# Sheet1.net
KiCad netlist of a schematic drawn in Altium Designer
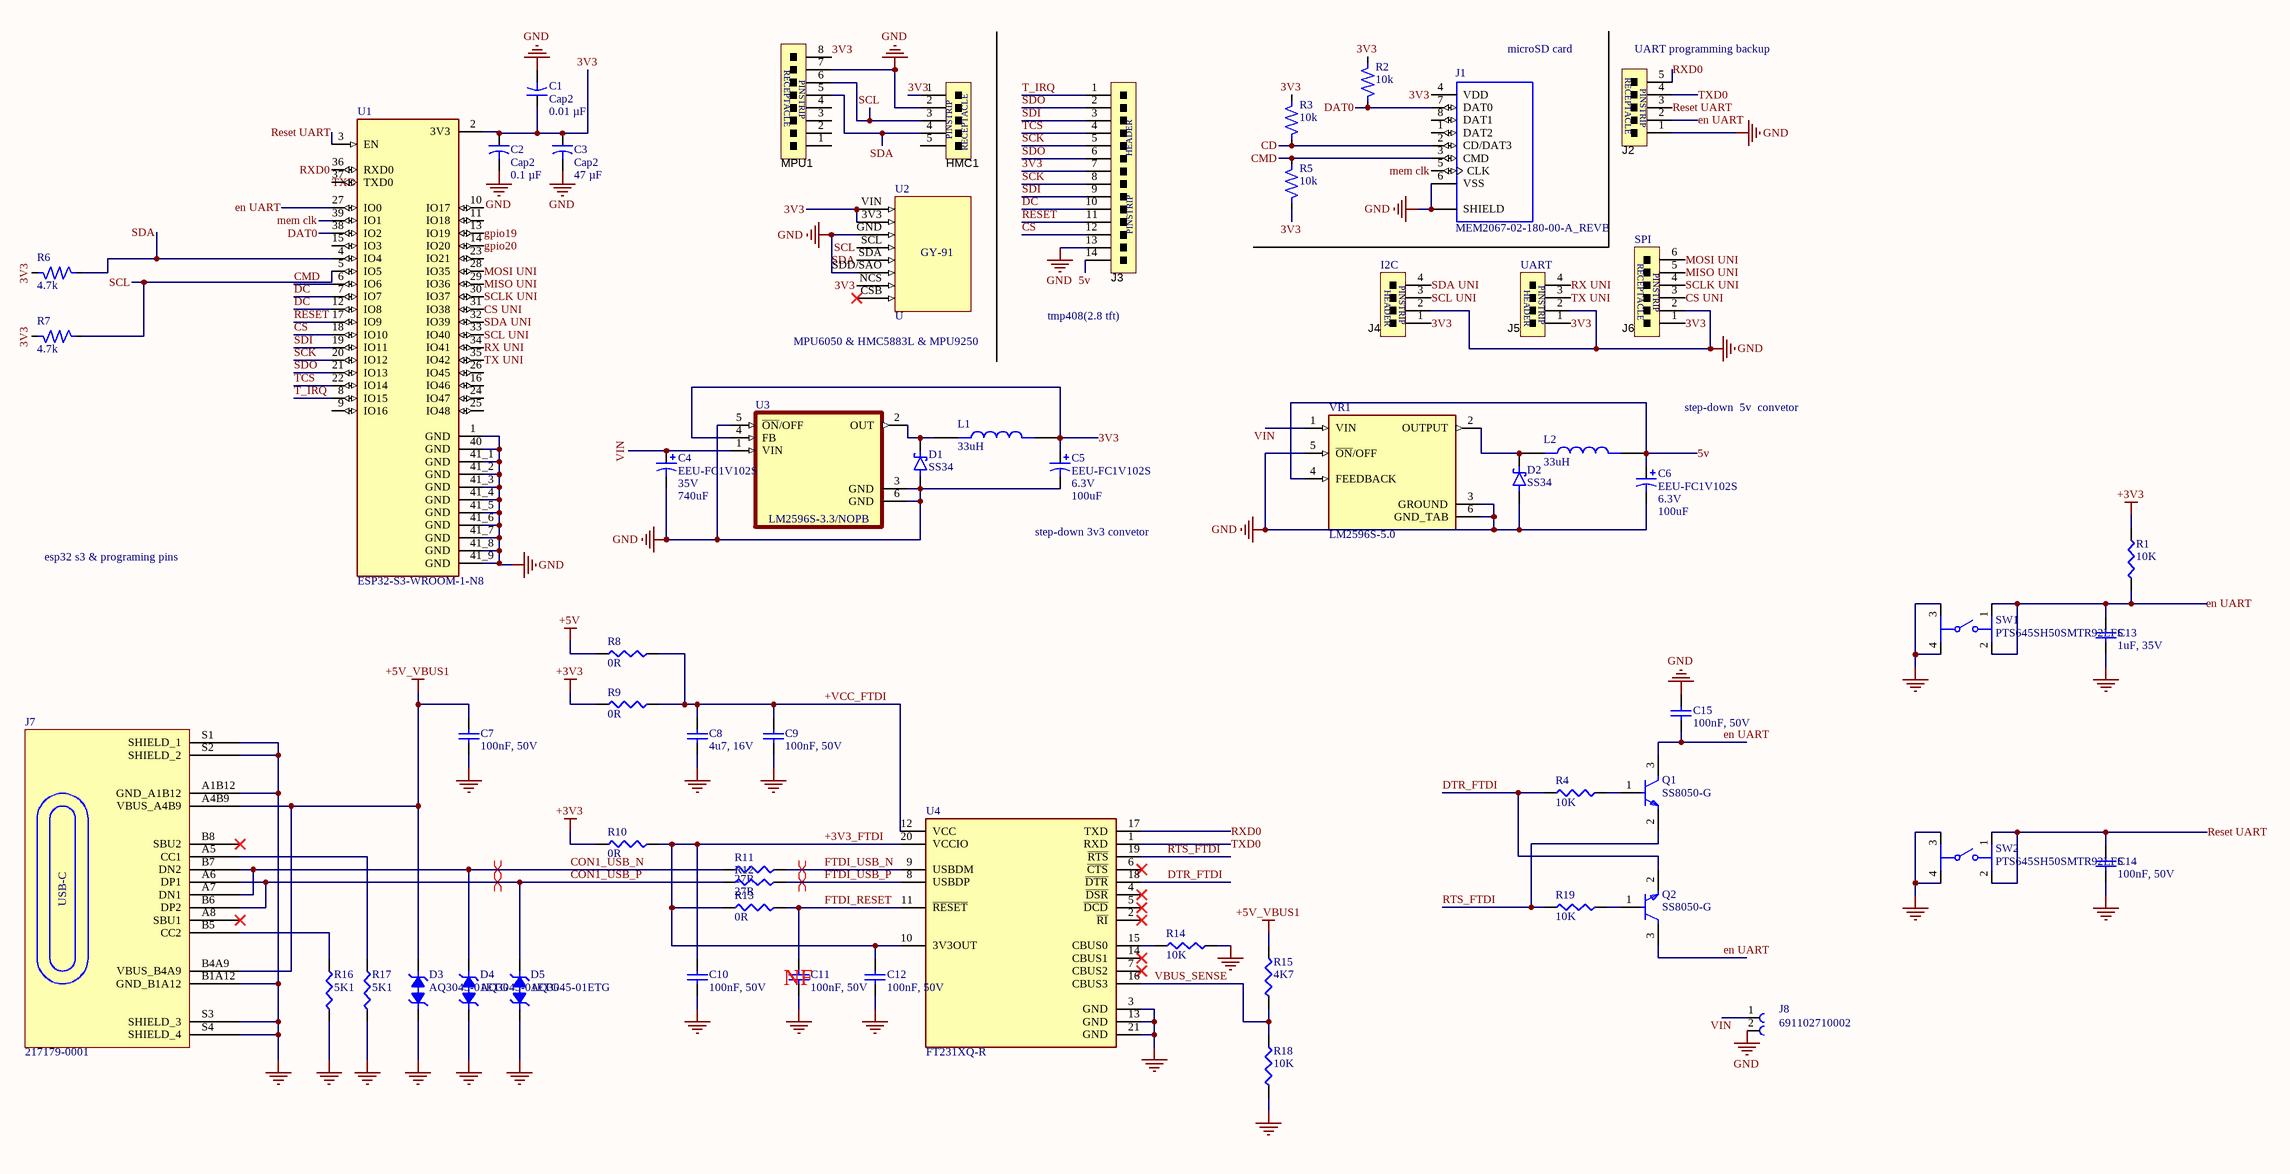
[diagram p0: Sheet1.SchDoc]

(export (version "E")
  (design (tool "Eeschema 10.0.6"))
  (components
    (comp (ref "C1")
      (value "Cap2")
      (footprint "CAPR5-4X5")
      (description "Capacitor")
      (fields (field (name "ALTIUM_VALUE") "0.01 µF") (field (name "PUBLISHER") "Altium Limited"))
      (libsource (lib "Miscellaneous Devices") (part "Cap2"))
    )
    (comp (ref "C2")
      (value "Cap2")
      (footprint "CAPR5-4X5")
      (description "Capacitor")
      (fields (field (name "ALTIUM_VALUE") "0.1 µF") (field (name "PUBLISHER") "Altium Limited"))
      (libsource (lib "Miscellaneous Devices") (part "Cap2"))
    )
    (comp (ref "C3")
      (value "Cap2")
      (footprint "CAPR5-4X5")
      (description "Capacitor")
      (fields (field (name "ALTIUM_VALUE") "47 µF") (field (name "PUBLISHER") "Altium Limited"))
      (libsource (lib "Miscellaneous Devices") (part "Cap2"))
    )
    (comp (ref "C4")
      (value "EEU-FC1V102S")
      (footprint "THRU-KMG-L25")
      (description "1000uF, Alum Electrolytic Capacitor, 35V, 16mm x 20mm, lead spacing 7.5mm")
      (fields
        (field (name "MANUFACTURER") "Panasonic")
        (field (name "VOLTAGEDC") "35V")
        (field (name "ALTIUM_VALUE") "740uF")
      )
      (libsource (lib "Caps") (part "1000uF"))
    )
    (comp (ref "C5")
      (value "EEU-FC1V102S")
      (footprint "THRU-KMG-L25")
      (description "1000uF, Alum Electrolytic Capacitor, 35V, 16mm x 20mm, lead spacing 7.5mm")
      (fields
        (field (name "MANUFACTURER") "Panasonic")
        (field (name "VOLTAGEDC") "6.3V")
        (field (name "ALTIUM_VALUE") "100uF")
      )
      (libsource (lib "Caps") (part "1000uF"))
    )
    (comp (ref "C6")
      (value "EEU-FC1V102S")
      (footprint "THRU-KMG-L25")
      (description "1000uF, Alum Electrolytic Capacitor, 35V, 16mm x 20mm, lead spacing 7.5mm")
      (fields
        (field (name "MANUFACTURER") "Panasonic")
        (field (name "VOLTAGEDC") "6.3V")
        (field (name "ALTIUM_VALUE") "100uF")
      )
      (libsource (lib "Caps") (part "1000uF"))
    )
    (comp (ref "C7")
      (value "100nF, 50V")
      (footprint "CAPC1005X55N")
      (description "CAP CER 0.1UF 50V X7R 0402")
      (fields
        (field (name "MANUFACTURER") "Samsung")
        (field (name "MANUFACTURER PART NUMBER") "CL05B104KB54PNC")
      )
      (libsource (lib "Schlib") (part "CL05B104KB54PNC"))
    )
    (comp (ref "C8")
      (value "4u7, 16V")
      (footprint "CAPC1005X55N")
      (description "CAP CER 4.7UF 16V X5R 0402")
      (fields
        (field (name "MANUFACTURER") "Samsung")
        (field (name "MANUFACTURER PART NUMBER") "CL05A475MO5NUNC")
      )
      (libsource (lib "Schlib") (part "CL05A475MO5NUNC"))
    )
    (comp (ref "C9")
      (value "100nF, 50V")
      (footprint "CAPC1005X55N")
      (description "CAP CER 0.1UF 50V X7R 0402")
      (fields
        (field (name "MANUFACTURER") "Samsung")
        (field (name "MANUFACTURER PART NUMBER") "CL05B104KB54PNC")
      )
      (libsource (lib "Schlib") (part "CL05B104KB54PNC"))
    )
    (comp (ref "C10")
      (value "100nF, 50V")
      (footprint "CAPC1005X55N")
      (description "CAP CER 0.1UF 50V X7R 0402")
      (fields
        (field (name "MANUFACTURER") "Samsung")
        (field (name "MANUFACTURER PART NUMBER") "CL05B104KB54PNC")
      )
      (libsource (lib "Schlib") (part "CL05B104KB54PNC"))
    )
    (comp (ref "C11")
      (value "100nF, 50V")
      (footprint "CAPC1005X55N")
      (description "CAP CER 0.1UF 50V X7R 0402")
      (fields
        (field (name "MANUFACTURER") "Samsung")
        (field (name "MANUFACTURER PART NUMBER") "CL05B104KB54PNC")
      )
      (libsource (lib "Schlib") (part "CL05B104KB54PNC"))
    )
    (comp (ref "C12")
      (value "100nF, 50V")
      (footprint "CAPC1005X55N")
      (description "CAP CER 0.1UF 50V X7R 0402")
      (fields
        (field (name "MANUFACTURER") "Samsung")
        (field (name "MANUFACTURER PART NUMBER") "CL05B104KB54PNC")
      )
      (libsource (lib "Schlib") (part "CL05B104KB54PNC"))
    )
    (comp (ref "C13")
      (value "1uF, 35V")
      (footprint "CAPC1005X55N")
      (description "CAP CER 1UF 35V X5R 0402")
      (fields
        (field (name "MANUFACTURER") "Samsung")
        (field (name "MANUFACTURER PART NUMBER") "CL05A105KL5NRNC")
      )
      (libsource (lib "Schlib") (part "CL05A105KL5NRNC"))
    )
    (comp (ref "C14")
      (value "100nF, 50V")
      (footprint "CAPC1005X55N")
      (description "CAP CER 0.1UF 50V X7R 0402")
      (fields
        (field (name "MANUFACTURER") "Samsung")
        (field (name "MANUFACTURER PART NUMBER") "CL05B104KB54PNC")
      )
      (libsource (lib "Schlib") (part "CL05B104KB54PNC"))
    )
    (comp (ref "C15")
      (value "100nF, 50V")
      (footprint "CAPC1005X55N")
      (description "CAP CER 0.1UF 50V X7R 0402")
      (fields
        (field (name "MANUFACTURER") "Samsung")
        (field (name "MANUFACTURER PART NUMBER") "CL05B104KB54PNC")
      )
      (libsource (lib "Schlib") (part "CL05B104KB54PNC"))
    )
    (comp (ref "D1")
      (value "SS34")
      (footprint "DIO_SS34")
      (description "3A, 40V, Schottky Rectifier")
      (fields (field (name "MF") "Taiwan Semiconductor"))
      (libsource (lib "SS34") (part "SS34"))
    )
    (comp (ref "D2")
      (value "SS34")
      (footprint "DIO_SS34")
      (description "3A, 40V, Schottky Rectifier")
      (fields (field (name "MF") "Taiwan Semiconductor"))
      (libsource (lib "SS34") (part "SS34"))
    )
    (comp (ref "D3")
      (value "AQ3045-01ETG")
      (footprint "SOD882")
      (description "TVS DIODE 5.3VWM 12VC SOD882")
      (fields (field (name "MANUFACTURER") "Littelfuse") (field (name "LCSC PART NUMBER") "C3710326"))
      (libsource (lib "Schlib") (part "AQ3045-01ETG"))
    )
    (comp (ref "D4")
      (value "AQ3045-01ETG")
      (footprint "SOD882")
      (description "TVS DIODE 5.3VWM 12VC SOD882")
      (fields (field (name "MANUFACTURER") "Littelfuse") (field (name "LCSC PART NUMBER") "C3710326"))
      (libsource (lib "Schlib") (part "AQ3045-01ETG"))
    )
    (comp (ref "D5")
      (value "AQ3045-01ETG")
      (footprint "SOD882")
      (description "TVS DIODE 5.3VWM 12VC SOD882")
      (fields (field (name "MANUFACTURER") "Littelfuse") (field (name "LCSC PART NUMBER") "C3710326"))
      (libsource (lib "Schlib") (part "AQ3045-01ETG"))
    )
    (comp (ref "HMC1")
      (value "5-534237-3")
      (footprint "PINSTRIP-SINGLE-5PIN-.1")
      (description "5 Pin Receptacle, Single row, 2.54mm pitch, Vertical")
      (fields (field (name "MANUFACTURER") "TE Connectivity"))
      (libsource (lib "CONNECTORS - PIN HEADERS") (part "PINSTRIP-RCPT-SINGLE-5pin"))
    )
    (comp (ref "J1")
      (value "MEM2067-02-180-00-A_REVB")
      (footprint "GCT_MEM2067-02-180-00-A_REVB")
      (description "Micro SD Memory Card ConnectorSMT, Hinged, 1.80mm Profile")
      (libsource (lib "MEM2067-02-180-00-A_REVB") (part "MEM2067-02-180-00-A_REVB"))
    )
    (comp (ref "J2")
      (value "5-534237-3")
      (footprint "PINSTRIP-SINGLE-5PIN-.1")
      (description "5 Pin Receptacle, Single row, 2.54mm pitch, Vertical")
      (fields (field (name "MANUFACTURER") "TE Connectivity"))
      (libsource (lib "") (part "PINSTRIP-RCPT-SINGLE-5pin_1"))
    )
    (comp (ref "J3")
      (value "9-146285-0")
      (footprint "PINSTRIP-SINGLE-14PIN-.1")
      (description "14 Pin Header, Single row, 2.54mm pitch, Unshrouded Pin Strip, Vertical")
      (fields
        (field (name "MANUFACTURER") "TE Connectivity")
        (field (name "PART NUMBER") "14/40 of 9-146285-0")
      )
      (libsource (lib "CONNECTORS - PIN HEADERS") (part "PINSTRIP-HDR-SINGLE-14pin"))
    )
    (comp (ref "J4")
      (value "9-146285-0")
      (footprint "PINSTRIP-SINGLE-4PIN-.1")
      (description "4 Pin Header, Single row, 2.54mm pitch, Unshrouded Pin Strip, Vertical")
      (fields
        (field (name "MANUFACTURER") "TE Connectivity")
        (field (name "PART NUMBER") "04/40 of 9-146285-0")
      )
      (libsource (lib "CONNECTORS - PIN HEADERS") (part "PINSTRIP-HDR-SINGLE-4pin"))
    )
    (comp (ref "J5")
      (value "9-146285-0")
      (footprint "PINSTRIP-SINGLE-4PIN-.1")
      (description "4 Pin Header, Single row, 2.54mm pitch, Unshrouded Pin Strip, Vertical")
      (fields
        (field (name "MANUFACTURER") "TE Connectivity")
        (field (name "PART NUMBER") "04/40 of 9-146285-0")
      )
      (libsource (lib "CONNECTORS - PIN HEADERS") (part "PINSTRIP-HDR-SINGLE-4pin"))
    )
    (comp (ref "J6")
      (value "5-534237-4")
      (footprint "PINSTRIP-SINGLE-6PIN-.1")
      (description "6 Pin Receptacle, Single row, 2.54mm pitch, Vertical")
      (fields (field (name "MANUFACTURER") "TE Connectivity"))
      (libsource (lib "CONNECTORS - PIN HEADERS") (part "PINSTRIP-RCPT-SINGLE-6pin"))
    )
    (comp (ref "J7")
      (value "217179-0001")
      (footprint "FP-2171790001-MFG")
      (description "CONN RCP USB2.0 TYP C 24P SMD RA")
      (fields (field (name "MANUFACTURER") "Molex") (field (name "LCSC PART NUMBER") "C3197684"))
      (libsource (lib "Schlib") (part "217179-0001"))
    )
    (comp (ref "J8")
      (value "691102710002")
      (footprint "*691102710002")
      (description "102 Series 5mm Pitch Straight, PCB Terminal Block, Through Hole, 2 Way")
      (fields (field (name "MF") "Wurth Electronics"))
      (libsource (lib "Terminal block") (part "691102710002"))
    )
    (comp (ref "L1")
      (value "33uH")
      (footprint "IND_FIT68-5")
      (description "33.15 ÂµH Unshielded Toroidal Inductor 5.7 A 28.8mOhm Max Radial, Vertical (Open)")
      (fields (field (name "MF") "Triad Magnetics") (field (name "MP") "FIT68-5"))
      (libsource (lib "FIT68-5") (part "FIT68-5"))
    )
    (comp (ref "L2")
      (value "33uH")
      (footprint "IND_FIT68-5")
      (description "33.15 ÂµH Unshielded Toroidal Inductor 5.7 A 28.8mOhm Max Radial, Vertical (Open)")
      (fields (field (name "MF") "Triad Magnetics") (field (name "MP") "FIT68-5"))
      (libsource (lib "FIT68-5") (part "FIT68-5"))
    )
    (comp (ref "MPU1")
      (value "5-534237-6")
      (footprint "PINSTRIP-SINGLE-8PIN-.1")
      (description "8 Pin Receptacle, Single row, 2.54mm pitch, Vertical")
      (fields (field (name "MANUFACTURER") "TE Connectivity"))
      (libsource (lib "CONNECTORS - PIN HEADERS") (part "PINSTRIP-RCPT-SINGLE-8pin"))
    )
    (comp (ref "Q1")
      (value "SS8050-G")
      (footprint "FP-SS8050-G-IPC_B")
      (description "TRANS NPN 25V 1.5A SOT23-3")
      (fields (field (name "MANUFACTURER") "Comchip") (field (name "LCSC PART NUMBER") "C164886"))
      (libsource (lib "Schlib") (part "SS8050-G"))
    )
    (comp (ref "Q2")
      (value "SS8050-G")
      (footprint "FP-SS8050-G-IPC_B")
      (description "TRANS NPN 25V 1.5A SOT23-3")
      (fields (field (name "MANUFACTURER") "Comchip") (field (name "LCSC PART NUMBER") "C164886"))
      (libsource (lib "Schlib") (part "SS8050-G"))
    )
    (comp (ref "R1")
      (value "10K")
      (footprint "RESC1005X37N")
      (description "RES SMD 10K OHM 1% 1/16W 0402")
      (fields
        (field (name "MANUFACTURER") "Yageo")
        (field (name "MANUFACTURER PART NUMBER") "AC0402FR-0710KL")
      )
      (libsource (lib "Schlib") (part "AC0402FR-0710KL"))
    )
    (comp (ref "R2")
      (value "10k")
      (footprint "R0805")
      (description "1.5kR, 0805 SMT resistor, 1/8W, 1%")
      (fields (field (name "Comment") "1.5kR, 0805"))
      (libsource (lib "Resistors") (part "1.5kR-0805"))
    )
    (comp (ref "R3")
      (value "10k")
      (footprint "R0805")
      (description "1.5kR, 0805 SMT resistor, 1/8W, 1%")
      (fields (field (name "Comment") "1.5kR, 0805"))
      (libsource (lib "Resistors") (part "1.5kR-0805"))
    )
    (comp (ref "R4")
      (value "10K")
      (footprint "RESC1005X37N")
      (description "RES SMD 10K OHM 1% 1/16W 0402")
      (fields
        (field (name "MANUFACTURER") "Yageo")
        (field (name "MANUFACTURER PART NUMBER") "AC0402FR-0710KL")
      )
      (libsource (lib "Schlib") (part "AC0402FR-0710KL"))
    )
    (comp (ref "R5")
      (value "10k")
      (footprint "R0805")
      (description "1.5kR, 0805 SMT resistor, 1/8W, 1%")
      (fields (field (name "Comment") "1.5kR, 0805"))
      (libsource (lib "Resistors") (part "1.5kR-0805"))
    )
    (comp (ref "R6")
      (value "4.7k")
      (footprint "R0805")
      (description "1.5kR, 0805 SMT resistor, 1/8W, 1%")
      (fields (field (name "Comment") "1.5kR, 0805"))
      (libsource (lib "Resistors") (part "1.5kR-0805"))
    )
    (comp (ref "R7")
      (value "4.7k")
      (footprint "R0805")
      (description "1.5kR, 0805 SMT resistor, 1/8W, 1%")
      (fields (field (name "Comment") "1.5kR, 0805"))
      (libsource (lib "Resistors") (part "1.5kR-0805"))
    )
    (comp (ref "R8")
      (value "0R")
      (footprint "RESC1005X37N")
      (description "RES 0 OHM JUMPER 1/16W 0402")
      (fields
        (field (name "MANUFACTURER") "Yageo")
        (field (name "MANUFACTURER PART NUMBER") "RC0402JR-070RL")
      )
      (libsource (lib "Schlib") (part "RC0402JR-070RL"))
    )
    (comp (ref "R9")
      (value "0R")
      (footprint "RESC1005X37N")
      (description "RES 0 OHM JUMPER 1/16W 0402")
      (fields
        (field (name "MANUFACTURER") "Yageo")
        (field (name "MANUFACTURER PART NUMBER") "RC0402JR-070RL")
      )
      (libsource (lib "Schlib") (part "RC0402JR-070RL"))
    )
    (comp (ref "R10")
      (value "0R")
      (footprint "RESC1005X37N")
      (description "RES 0 OHM JUMPER 1/16W 0402")
      (fields
        (field (name "MANUFACTURER") "Yageo")
        (field (name "MANUFACTURER PART NUMBER") "RC0402JR-070RL")
      )
      (libsource (lib "Schlib") (part "RC0402JR-070RL"))
    )
    (comp (ref "R11")
      (value "27R")
      (footprint "RESC1005X37N")
      (description "RES 27 OHM 1% 1/16W 0402")
      (fields
        (field (name "MANUFACTURER") "Yageo")
        (field (name "MANUFACTURER PART NUMBER") "RC0402FR-0727RL")
      )
      (libsource (lib "Schlib") (part "RC0402FR-0727RL"))
    )
    (comp (ref "R12")
      (value "27R")
      (footprint "RESC1005X37N")
      (description "RES 27 OHM 1% 1/16W 0402")
      (fields
        (field (name "MANUFACTURER") "Yageo")
        (field (name "MANUFACTURER PART NUMBER") "RC0402FR-0727RL")
      )
      (libsource (lib "Schlib") (part "RC0402FR-0727RL"))
    )
    (comp (ref "R13")
      (value "0R")
      (footprint "RESC1005X37N")
      (description "RES 0 OHM JUMPER 1/16W 0402")
      (fields
        (field (name "MANUFACTURER") "Yageo")
        (field (name "MANUFACTURER PART NUMBER") "RC0402JR-070RL")
      )
      (libsource (lib "Schlib") (part "RC0402JR-070RL"))
    )
    (comp (ref "R14")
      (value "10K")
      (footprint "RESC1005X37N")
      (description "RES SMD 10K OHM 1% 1/16W 0402")
      (fields
        (field (name "MANUFACTURER") "Yageo")
        (field (name "MANUFACTURER PART NUMBER") "AC0402FR-0710KL")
      )
      (libsource (lib "Schlib") (part "AC0402FR-0710KL"))
    )
    (comp (ref "R15")
      (value "4K7")
      (footprint "RESC1005X37N")
      (description "RES 4.7K OHM 1% 1/16W 0402")
      (fields
        (field (name "MANUFACTURER") "Yageo")
        (field (name "MANUFACTURER PART NUMBER") "RC0402FR-074K7L")
      )
      (libsource (lib "Schlib") (part "RC0402FR-074K7L"))
    )
    (comp (ref "R16")
      (value "5K1")
      (footprint "RESC1005X37N")
      (description "RES SMD 5.1K OHM 1% 1/16W 0402")
      (fields
        (field (name "MANUFACTURER") "Yageo")
        (field (name "MANUFACTURER PART NUMBER") "AC0402FR-075K1L")
      )
      (libsource (lib "Schlib") (part "AC0402FR-075K1L"))
    )
    (comp (ref "R17")
      (value "5K1")
      (footprint "RESC1005X37N")
      (description "RES SMD 5.1K OHM 1% 1/16W 0402")
      (fields
        (field (name "MANUFACTURER") "Yageo")
        (field (name "MANUFACTURER PART NUMBER") "AC0402FR-075K1L")
      )
      (libsource (lib "Schlib") (part "AC0402FR-075K1L"))
    )
    (comp (ref "R18")
      (value "10K")
      (footprint "RESC1005X37N")
      (description "RES SMD 10K OHM 1% 1/16W 0402")
      (fields
        (field (name "MANUFACTURER") "Yageo")
        (field (name "MANUFACTURER PART NUMBER") "AC0402FR-0710KL")
      )
      (libsource (lib "Schlib") (part "AC0402FR-0710KL"))
    )
    (comp (ref "R19")
      (value "10K")
      (footprint "RESC1005X37N")
      (description "RES SMD 10K OHM 1% 1/16W 0402")
      (fields
        (field (name "MANUFACTURER") "Yageo")
        (field (name "MANUFACTURER PART NUMBER") "AC0402FR-0710KL")
      )
      (libsource (lib "Schlib") (part "AC0402FR-0710KL"))
    )
    (comp (ref "SW1")
      (value "PTS645SH50SMTR92LFS")
      (footprint "FP-PTS645SH50SMTR92LFS-MFG")
      (description "SWITCH TACTILE SPST-NO 0.05A 12V")
      (fields (field (name "MANUFACTURER") "ITT C&K") (field (name "LCSC PART NUMBER") "C221869"))
      (libsource (lib "Schlib") (part "PTS645SH50SMTR92LFS"))
    )
    (comp (ref "SW2")
      (value "PTS645SH50SMTR92LFS")
      (footprint "FP-PTS645SH50SMTR92LFS-MFG")
      (description "SWITCH TACTILE SPST-NO 0.05A 12V")
      (fields (field (name "MANUFACTURER") "ITT C&K") (field (name "LCSC PART NUMBER") "C221869"))
      (libsource (lib "Schlib") (part "PTS645SH50SMTR92LFS"))
    )
    (comp (ref "U1")
      (value "ESP32-S3-WROOM-1-N8")
      (footprint "XCVR_ESP32-S3-WROOM-1-N8")
      (fields (field (name "MF") "{'manufacturer': u'Espressif Systems'}"))
      (libsource (lib "ESP32-S3-WROOM-1-N8(1)") (part "ESP32-S3-WROOM-1-N8"))
    )
    (comp (ref "U2") (value "U") (footprint "GY-91") (libsource (lib "GY-91") (part "GY-91")))
    (comp (ref "U3")
      (value "LM2596S-3.3/NOPB")
      (footprint "VREG_LM2596S-3.3/NOPB")
      (description "SIMPLE SWITCHERÂ® 4.5V to 40V, 3A Low Component Count Step-Down Regulator 5-DDPAK/TO-263")
      (fields (field (name "MF") "Texas Instruments") (field (name "MP") "LM2596S-3.3"))
      (libsource (lib "LM2596S-3.3_NOPB") (part "LM2596S-3.3/NOPB"))
    )
    (comp (ref "U4")
      (value "FT231XQ-R")
      (footprint "FP-QFN-20-IPC_B")
      (description "IC USB SERIAL FULL UART 20QFN")
      (fields (field (name "MANUFACTURER") "FTDI") (field (name "LCSC PART NUMBER") "C132159"))
      (libsource (lib "Schlib") (part "FT231XQ-R"))
    )
    (comp (ref "VR1")
      (value "LM2596S-5.0")
      (footprint "TO170P1524X483-6N")
      (description "SIMPLE SWITCHERÂ® 4.5V to 40V, 3A Low Component Count Step-Down Regulator")
      (fields (field (name "MF") "Texas Instruments") (field (name "MP") "LM2596S-5.0/NOPB"))
      (libsource (lib "LM2596S-5.0") (part "LM2596S-5.0"))
    )
  )
  (nets
    (net (code "1") (name "+3V3") (class "Default")
      (node (ref "R1") (pin "2") (pinfunction "2_2") (pintype "passive"))
      (node (ref "R10") (pin "1") (pinfunction "1_1") (pintype "passive"))
      (node (ref "R9") (pin "1") (pinfunction "1_1") (pintype "passive"))
    )
    (net (code "2") (name "+5V") (class "Default")
      (node (ref "R8") (pin "1") (pinfunction "1_1") (pintype "passive"))
    )
    (net (code "3") (name "+5V_VBUS1") (class "Default")
      (node (ref "C7") (pin "2") (pinfunction "2_2") (pintype "passive"))
      (node (ref "D3") (pin "2") (pinfunction "2_2") (pintype "passive"))
      (node (ref "J7") (pin "A4B9") (pinfunction "VBUS_A4B9_A4B9") (pintype "passive"))
      (node (ref "J7") (pin "B4A9") (pinfunction "VBUS_B4A9_B4A9") (pintype "passive"))
      (node (ref "R15") (pin "2") (pinfunction "2_2") (pintype "passive"))
    )
    (net (code "4") (name "/+3V3_FTDI") (class "Default")
      (node (ref "C10") (pin "2") (pinfunction "2_2") (pintype "passive"))
      (node (ref "C12") (pin "2") (pinfunction "2_2") (pintype "passive"))
      (node (ref "R10") (pin "2") (pinfunction "2_2") (pintype "passive"))
      (node (ref "R13") (pin "1") (pinfunction "1_1") (pintype "passive"))
      (node (ref "U4") (pin "10") (pinfunction "3V3OUT_10") (pintype "passive"))
      (node (ref "U4") (pin "20") (pinfunction "VCCIO_20") (pintype "passive"))
    )
    (net (code "5") (name "/+VCC_FTDI") (class "Default")
      (node (ref "C8") (pin "2") (pinfunction "2_2") (pintype "passive"))
      (node (ref "C9") (pin "2") (pinfunction "2_2") (pintype "passive"))
      (node (ref "R8") (pin "2") (pinfunction "2_2") (pintype "passive"))
      (node (ref "R9") (pin "2") (pinfunction "2_2") (pintype "passive"))
      (node (ref "U4") (pin "12") (pinfunction "VCC_12") (pintype "passive"))
    )
    (net (code "6") (name "/3V3") (class "Default")
      (node (ref "C1") (pin "1") (pinfunction "1_1") (pintype "passive"))
      (node (ref "C2") (pin "1") (pinfunction "1_1") (pintype "passive"))
      (node (ref "C3") (pin "1") (pinfunction "1_1") (pintype "passive"))
      (node (ref "C5") (pin "1") (pinfunction "1_1") (pintype "passive"))
      (node (ref "HMC1") (pin "1") (pinfunction "Vcc_1") (pintype "passive"))
      (node (ref "J1") (pin "4") (pinfunction "VDD_4") (pintype "power_in"))
      (node (ref "J3") (pin "7") (pinfunction "7_7") (pintype "passive"))
      (node (ref "J4") (pin "1") (pinfunction "1_1") (pintype "passive"))
      (node (ref "J5") (pin "1") (pinfunction "1_1") (pintype "passive"))
      (node (ref "J6") (pin "1") (pinfunction "1_1") (pintype "passive"))
      (node (ref "L1") (pin "2") (pinfunction "2_2") (pintype "passive"))
      (node (ref "MPU1") (pin "8") (pinfunction "8_8") (pintype "passive"))
      (node (ref "R2") (pin "2") (pinfunction "2_2") (pintype "passive"))
      (node (ref "R3") (pin "2") (pinfunction "2_2") (pintype "passive"))
      (node (ref "R5") (pin "1") (pinfunction "1_1") (pintype "passive"))
      (node (ref "R6") (pin "1") (pinfunction "1_1") (pintype "passive"))
      (node (ref "R7") (pin "1") (pinfunction "1_1") (pintype "passive"))
      (node (ref "U1") (pin "2") (pinfunction "3V3_2") (pintype "power_in"))
      (node (ref "U2") (pin "3V3") (pintype "input"))
      (node (ref "U2") (pin "NCS") (pintype "input"))
      (node (ref "U2") (pin "VIN") (pintype "input"))
      (node (ref "U3") (pin "4") (pinfunction "FB_4") (pintype "input"))
    )
    (net (code "7") (name "/5v") (class "Default")
      (node (ref "C6") (pin "1") (pinfunction "1_1") (pintype "passive"))
      (node (ref "J3") (pin "14") (pinfunction "14_14") (pintype "passive"))
      (node (ref "L2") (pin "2") (pinfunction "2_2") (pintype "passive"))
      (node (ref "VR1") (pin "4") (pinfunction "FEEDBACK_4") (pintype "input"))
    )
    (net (code "8") (name "/CD") (class "Default")
      (node (ref "J1") (pin "2") (pinfunction "CD/DAT3_2") (pintype "bidirectional"))
      (node (ref "R3") (pin "1") (pinfunction "1_1") (pintype "passive"))
    )
    (net (code "9") (name "/CMD") (class "Default")
      (node (ref "J1") (pin "3") (pinfunction "CMD_3") (pintype "bidirectional"))
      (node (ref "R5") (pin "2") (pinfunction "2_2") (pintype "passive"))
      (node (ref "U1") (pin "6") (pinfunction "IO6_6") (pintype "bidirectional"))
    )
    (net (code "10") (name "/CON1_USB_N") (class "Default")
      (node (ref "D4") (pin "2") (pinfunction "2_2") (pintype "passive"))
      (node (ref "J7") (pin "A7") (pinfunction "DN1_A7") (pintype "passive"))
      (node (ref "J7") (pin "B7") (pinfunction "DN2_B7") (pintype "passive"))
      (node (ref "R11") (pin "1") (pinfunction "1_1") (pintype "passive"))
    )
    (net (code "11") (name "/CON1_USB_P") (class "Default")
      (node (ref "D5") (pin "2") (pinfunction "2_2") (pintype "passive"))
      (node (ref "J7") (pin "A6") (pinfunction "DP1_A6") (pintype "passive"))
      (node (ref "J7") (pin "B6") (pinfunction "DP2_B6") (pintype "passive"))
      (node (ref "R12") (pin "1") (pinfunction "1_1") (pintype "passive"))
    )
    (net (code "12") (name "/CS") (class "Default")
      (node (ref "J3") (pin "12") (pinfunction "12_12") (pintype "passive"))
      (node (ref "U1") (pin "18") (pinfunction "IO10_18") (pintype "bidirectional"))
    )
    (net (code "13") (name "/CS UNI") (class "Default")
      (node (ref "J6") (pin "3") (pinfunction "3_3") (pintype "passive"))
      (node (ref "U1") (pin "31") (pinfunction "IO38_31") (pintype "bidirectional"))
    )
    (net (code "14") (name "/DAT0") (class "Default")
      (node (ref "J1") (pin "7") (pinfunction "DAT0_7") (pintype "bidirectional"))
      (node (ref "R2") (pin "1") (pinfunction "1_1") (pintype "passive"))
      (node (ref "U1") (pin "38") (pinfunction "IO2_38") (pintype "bidirectional"))
    )
    (net (code "15") (name "/DC") (class "Default")
      (node (ref "J3") (pin "10") (pinfunction "10_10") (pintype "passive"))
      (node (ref "U1") (pin "12") (pinfunction "IO8_12") (pintype "bidirectional"))
      (node (ref "U1") (pin "7") (pinfunction "IO7_7") (pintype "bidirectional"))
    )
    (net (code "16") (name "/DTR_FTDI") (class "Default")
      (node (ref "Q2") (pin "2") (pinfunction "E_2") (pintype "passive"))
      (node (ref "R4") (pin "1") (pinfunction "1_1") (pintype "passive"))
      (node (ref "U4") (pin "18") (pinfunction "~{DTR}_18") (pintype "passive"))
    )
    (net (code "17") (name "/FTDI_RESET") (class "Default")
      (node (ref "C11") (pin "2") (pinfunction "2_2") (pintype "passive"))
      (node (ref "R13") (pin "2") (pinfunction "2_2") (pintype "passive"))
      (node (ref "U4") (pin "11") (pinfunction "~{RESET}_11") (pintype "passive"))
    )
    (net (code "18") (name "/FTDI_USB_N") (class "Default")
      (node (ref "R11") (pin "2") (pinfunction "2_2") (pintype "passive"))
      (node (ref "U4") (pin "9") (pinfunction "USBDM_9") (pintype "passive"))
    )
    (net (code "19") (name "/FTDI_USB_P") (class "Default")
      (node (ref "R12") (pin "2") (pinfunction "2_2") (pintype "passive"))
      (node (ref "U4") (pin "8") (pinfunction "USBDP_8") (pintype "passive"))
    )
    (net (code "20") (name "/MISO UNI") (class "Default")
      (node (ref "J6") (pin "5") (pinfunction "5_5") (pintype "passive"))
      (node (ref "U1") (pin "29") (pinfunction "IO36_29") (pintype "bidirectional"))
    )
    (net (code "21") (name "/MOSI UNI") (class "Default")
      (node (ref "J6") (pin "6") (pinfunction "6_6") (pintype "passive"))
      (node (ref "U1") (pin "28") (pinfunction "IO35_28") (pintype "bidirectional"))
    )
    (net (code "22") (name "/RESET") (class "Default")
      (node (ref "J3") (pin "11") (pinfunction "11_11") (pintype "passive"))
      (node (ref "U1") (pin "17") (pinfunction "IO9_17") (pintype "bidirectional"))
    )
    (net (code "23") (name "/RTS_FTDI") (class "Default")
      (node (ref "Q1") (pin "2") (pinfunction "E_2") (pintype "passive"))
      (node (ref "R19") (pin "1") (pinfunction "1_1") (pintype "passive"))
      (node (ref "U4") (pin "19") (pinfunction "~{RTS}_19") (pintype "passive"))
    )
    (net (code "24") (name "/RX UNI") (class "Default")
      (node (ref "J5") (pin "4") (pinfunction "4_4") (pintype "passive"))
      (node (ref "U1") (pin "34") (pinfunction "IO41_34") (pintype "bidirectional"))
    )
    (net (code "25") (name "/RXD0") (class "Default")
      (node (ref "J2") (pin "5") (pinfunction "5_5") (pintype "passive"))
      (node (ref "U1") (pin "36") (pinfunction "RXD0_36") (pintype "bidirectional"))
      (node (ref "U4") (pin "17") (pinfunction "TXD_17") (pintype "passive"))
    )
    (net (code "26") (name "/Reset UART") (class "Default")
      (node (ref "C14") (pin "2") (pinfunction "2_2") (pintype "passive"))
      (node (ref "J2") (pin "3") (pinfunction "3_3") (pintype "passive"))
      (node (ref "SW2") (pin "1") (pinfunction "1_1") (pintype "passive"))
      (node (ref "SW2") (pin "2") (pinfunction "2_2") (pintype "passive"))
      (node (ref "U1") (pin "3") (pinfunction "EN_3") (pintype "input"))
    )
    (net (code "27") (name "/SCK") (class "Default")
      (node (ref "J3") (pin "5") (pinfunction "5_5") (pintype "passive"))
      (node (ref "J3") (pin "8") (pinfunction "8_8") (pintype "passive"))
      (node (ref "U1") (pin "20") (pinfunction "IO12_20") (pintype "bidirectional"))
    )
    (net (code "28") (name "/SCL") (class "Default")
      (node (ref "HMC1") (pin "3") (pinfunction "SCL_3") (pintype "passive"))
      (node (ref "MPU1") (pin "6") (pinfunction "6_6") (pintype "passive"))
      (node (ref "R7") (pin "2") (pinfunction "2_2") (pintype "passive"))
      (node (ref "U1") (pin "5") (pinfunction "IO5_5") (pintype "bidirectional"))
      (node (ref "U2") (pin "SCL") (pintype "input"))
    )
    (net (code "29") (name "/SCL UNI") (class "Default")
      (node (ref "J4") (pin "3") (pinfunction "3_3") (pintype "passive"))
      (node (ref "U1") (pin "33") (pinfunction "IO40_33") (pintype "bidirectional"))
    )
    (net (code "30") (name "/SCLK UNI") (class "Default")
      (node (ref "J6") (pin "4") (pinfunction "4_4") (pintype "passive"))
      (node (ref "U1") (pin "30") (pinfunction "IO37_30") (pintype "bidirectional"))
    )
    (net (code "31") (name "/SDA") (class "Default")
      (node (ref "HMC1") (pin "4") (pinfunction "SDA_4") (pintype "passive"))
      (node (ref "MPU1") (pin "5") (pinfunction "5_5") (pintype "passive"))
      (node (ref "R6") (pin "2") (pinfunction "2_2") (pintype "passive"))
      (node (ref "U1") (pin "4") (pinfunction "IO4_4") (pintype "bidirectional"))
      (node (ref "U2") (pin "SDA") (pintype "input"))
    )
    (net (code "32") (name "/SDA UNI") (class "Default")
      (node (ref "J4") (pin "4") (pinfunction "4_4") (pintype "passive"))
      (node (ref "U1") (pin "32") (pinfunction "IO39_32") (pintype "bidirectional"))
    )
    (net (code "33") (name "/SDI") (class "Default")
      (node (ref "J3") (pin "3") (pinfunction "3_3") (pintype "passive"))
      (node (ref "J3") (pin "9") (pinfunction "9_9") (pintype "passive"))
      (node (ref "U1") (pin "19") (pinfunction "IO11_19") (pintype "bidirectional"))
    )
    (net (code "34") (name "/SDO") (class "Default")
      (node (ref "J3") (pin "2") (pinfunction "2_2") (pintype "passive"))
      (node (ref "J3") (pin "6") (pinfunction "6_6") (pintype "passive"))
      (node (ref "U1") (pin "21") (pinfunction "IO13_21") (pintype "bidirectional"))
    )
    (net (code "35") (name "/TCS") (class "Default")
      (node (ref "J3") (pin "4") (pinfunction "4_4") (pintype "passive"))
      (node (ref "U1") (pin "22") (pinfunction "IO14_22") (pintype "bidirectional"))
    )
    (net (code "36") (name "/TX UNI") (class "Default")
      (node (ref "J5") (pin "3") (pinfunction "3_3") (pintype "passive"))
      (node (ref "U1") (pin "35") (pinfunction "IO42_35") (pintype "bidirectional"))
    )
    (net (code "37") (name "/TXD0") (class "Default")
      (node (ref "J2") (pin "4") (pinfunction "4_4") (pintype "passive"))
      (node (ref "U1") (pin "37") (pinfunction "TXD0_37") (pintype "bidirectional"))
      (node (ref "U4") (pin "1") (pinfunction "RXD_1") (pintype "passive"))
    )
    (net (code "38") (name "/T_IRQ") (class "Default")
      (node (ref "J3") (pin "1") (pinfunction "1_1") (pintype "passive"))
      (node (ref "U1") (pin "8") (pinfunction "IO15_8") (pintype "bidirectional"))
    )
    (net (code "39") (name "/VBUS_SENSE") (class "Default")
      (node (ref "R15") (pin "1") (pinfunction "1_1") (pintype "passive"))
      (node (ref "R18") (pin "1") (pinfunction "1_1") (pintype "passive"))
      (node (ref "U4") (pin "16") (pinfunction "CBUS3_16") (pintype "passive"))
    )
    (net (code "40") (name "/VIN") (class "Default")
      (node (ref "C4") (pin "1") (pinfunction "1_1") (pintype "passive"))
      (node (ref "J8") (pin "1") (pinfunction "1_1") (pintype "passive"))
      (node (ref "U3") (pin "1") (pinfunction "VIN_1") (pintype "input"))
      (node (ref "VR1") (pin "1") (pinfunction "VIN_1") (pintype "input"))
    )
    (net (code "41") (name "/en UART") (class "Default")
      (node (ref "C13") (pin "2") (pinfunction "2_2") (pintype "passive"))
      (node (ref "C15") (pin "1") (pinfunction "1_1") (pintype "passive"))
      (node (ref "J2") (pin "2") (pinfunction "2_2") (pintype "passive"))
      (node (ref "Q1") (pin "3") (pinfunction "C_3") (pintype "passive"))
      (node (ref "Q2") (pin "3") (pinfunction "C_3") (pintype "passive"))
      (node (ref "R1") (pin "1") (pinfunction "1_1") (pintype "passive"))
      (node (ref "SW1") (pin "1") (pinfunction "1_1") (pintype "passive"))
      (node (ref "SW1") (pin "2") (pinfunction "2_2") (pintype "passive"))
      (node (ref "U1") (pin "27") (pinfunction "IO0_27") (pintype "bidirectional"))
    )
    (net (code "42") (name "/gpio19") (class "Default")
      (node (ref "U1") (pin "13") (pinfunction "IO19_13") (pintype "bidirectional"))
    )
    (net (code "43") (name "/gpio20") (class "Default")
      (node (ref "U1") (pin "14") (pinfunction "IO20_14") (pintype "bidirectional"))
    )
    (net (code "44") (name "/mem clk") (class "Default")
      (node (ref "J1") (pin "5") (pinfunction "CLK_5") (pintype "bidirectional"))
      (node (ref "U1") (pin "39") (pinfunction "IO1_39") (pintype "bidirectional"))
    )
    (net (code "45") (name "GND") (class "Default")
      (node (ref "C1") (pin "2") (pinfunction "2_2") (pintype "passive"))
      (node (ref "C10") (pin "1") (pinfunction "1_1") (pintype "passive"))
      (node (ref "C11") (pin "1") (pinfunction "1_1") (pintype "passive"))
      (node (ref "C12") (pin "1") (pinfunction "1_1") (pintype "passive"))
      (node (ref "C13") (pin "1") (pinfunction "1_1") (pintype "passive"))
      (node (ref "C14") (pin "1") (pinfunction "1_1") (pintype "passive"))
      (node (ref "C15") (pin "2") (pinfunction "2_2") (pintype "passive"))
      (node (ref "C2") (pin "2") (pinfunction "2_2") (pintype "passive"))
      (node (ref "C3") (pin "2") (pinfunction "2_2") (pintype "passive"))
      (node (ref "C4") (pin "2") (pinfunction "2_2") (pintype "passive"))
      (node (ref "C5") (pin "2") (pinfunction "2_2") (pintype "passive"))
      (node (ref "C6") (pin "2") (pinfunction "2_2") (pintype "passive"))
      (node (ref "C7") (pin "1") (pinfunction "1_1") (pintype "passive"))
      (node (ref "C8") (pin "1") (pinfunction "1_1") (pintype "passive"))
      (node (ref "C9") (pin "1") (pinfunction "1_1") (pintype "passive"))
      (node (ref "D1") (pin "A") (pinfunction "A_A") (pintype "passive"))
      (node (ref "D2") (pin "A") (pinfunction "A_A") (pintype "passive"))
      (node (ref "D3") (pin "1") (pinfunction "1_1") (pintype "passive"))
      (node (ref "D4") (pin "1") (pinfunction "1_1") (pintype "passive"))
      (node (ref "D5") (pin "1") (pinfunction "1_1") (pintype "passive"))
      (node (ref "HMC1") (pin "2") (pinfunction "GND_2") (pintype "passive"))
      (node (ref "J1") (pin "10") (pinfunction "SHIELD_10") (pintype "passive"))
      (node (ref "J1") (pin "11") (pinfunction "SHIELD_11") (pintype "passive"))
      (node (ref "J1") (pin "12") (pinfunction "SHIELD_12") (pintype "passive"))
      (node (ref "J1") (pin "6") (pinfunction "VSS_6") (pintype "power_in"))
      (node (ref "J1") (pin "9") (pinfunction "SHIELD_9") (pintype "passive"))
      (node (ref "J2") (pin "1") (pinfunction "1_1") (pintype "passive"))
      (node (ref "J3") (pin "13") (pinfunction "13_13") (pintype "passive"))
      (node (ref "J4") (pin "2") (pinfunction "2_2") (pintype "passive"))
      (node (ref "J5") (pin "2") (pinfunction "2_2") (pintype "passive"))
      (node (ref "J6") (pin "2") (pinfunction "2_2") (pintype "passive"))
      (node (ref "J7") (pin "A1B12") (pinfunction "GND_A1B12_A1B12") (pintype "passive"))
      (node (ref "J7") (pin "B1A12") (pinfunction "GND_B1A12_B1A12") (pintype "passive"))
      (node (ref "J7") (pin "S1") (pinfunction "SHIELD_1_S1") (pintype "passive"))
      (node (ref "J7") (pin "S2") (pinfunction "SHIELD_2_S2") (pintype "passive"))
      (node (ref "J7") (pin "S3") (pinfunction "SHIELD_3_S3") (pintype "passive"))
      (node (ref "J7") (pin "S4") (pinfunction "SHIELD_4_S4") (pintype "passive"))
      (node (ref "J8") (pin "2") (pinfunction "2_2") (pintype "passive"))
      (node (ref "MPU1") (pin "7") (pinfunction "7_7") (pintype "passive"))
      (node (ref "R14") (pin "2") (pinfunction "2_2") (pintype "passive"))
      (node (ref "R16") (pin "1") (pinfunction "1_1") (pintype "passive"))
      (node (ref "R17") (pin "1") (pinfunction "1_1") (pintype "passive"))
      (node (ref "R18") (pin "2") (pinfunction "2_2") (pintype "passive"))
      (node (ref "SW1") (pin "3") (pinfunction "3_3") (pintype "passive"))
      (node (ref "SW1") (pin "4") (pinfunction "4_4") (pintype "passive"))
      (node (ref "SW2") (pin "3") (pinfunction "3_3") (pintype "passive"))
      (node (ref "SW2") (pin "4") (pinfunction "4_4") (pintype "passive"))
      (node (ref "U1") (pin "1") (pinfunction "GND_1") (pintype "power_in"))
      (node (ref "U1") (pin "40") (pinfunction "GND_40") (pintype "power_in"))
      (node (ref "U1") (pin "41_1") (pinfunction "GND_41_1") (pintype "power_in"))
      (node (ref "U1") (pin "41_2") (pinfunction "GND_41_2") (pintype "power_in"))
      (node (ref "U1") (pin "41_3") (pinfunction "GND_41_3") (pintype "power_in"))
      (node (ref "U1") (pin "41_4") (pinfunction "GND_41_4") (pintype "power_in"))
      (node (ref "U1") (pin "41_5") (pinfunction "GND_41_5") (pintype "power_in"))
      (node (ref "U1") (pin "41_6") (pinfunction "GND_41_6") (pintype "power_in"))
      (node (ref "U1") (pin "41_7") (pinfunction "GND_41_7") (pintype "power_in"))
      (node (ref "U1") (pin "41_8") (pinfunction "GND_41_8") (pintype "power_in"))
      (node (ref "U1") (pin "41_9") (pinfunction "GND_41_9") (pintype "power_in"))
      (node (ref "U2") (pin "GND") (pintype "input"))
      (node (ref "U2") (pin "SDD/SAO") (pintype "input"))
      (node (ref "U3") (pin "3") (pinfunction "GND_3") (pintype "power_in"))
      (node (ref "U3") (pin "5") (pinfunction "~{ON}/OFF_5") (pintype "input"))
      (node (ref "U3") (pin "6") (pinfunction "GND_6") (pintype "power_in"))
      (node (ref "U4") (pin "13") (pinfunction "GND_13") (pintype "passive"))
      (node (ref "U4") (pin "21") (pinfunction "GND_21") (pintype "passive"))
      (node (ref "U4") (pin "3") (pinfunction "GND_3") (pintype "passive"))
      (node (ref "VR1") (pin "3") (pinfunction "GROUND_3") (pintype "power_in"))
      (node (ref "VR1") (pin "5") (pinfunction "~{ON}/OFF_5") (pintype "input"))
      (node (ref "VR1") (pin "6") (pinfunction "GND_TAB_6") (pintype "power_in"))
    )
    (net (code "46") (name "Net-(D1-K)") (class "Default")
      (node (ref "D1") (pin "C") (pinfunction "K_C") (pintype "passive"))
      (node (ref "L1") (pin "1") (pinfunction "1_1") (pintype "passive"))
      (node (ref "U3") (pin "2") (pinfunction "OUT_2") (pintype "output"))
    )
    (net (code "47") (name "Net-(D2-K)") (class "Default")
      (node (ref "D2") (pin "C") (pinfunction "K_C") (pintype "passive"))
      (node (ref "L2") (pin "1") (pinfunction "1_1") (pintype "passive"))
      (node (ref "VR1") (pin "2") (pinfunction "OUTPUT_2") (pintype "output"))
    )
    (net (code "48") (name "Net-(J7-CC1)") (class "Default")
      (node (ref "J7") (pin "A5") (pinfunction "CC1_A5") (pintype "passive"))
      (node (ref "R17") (pin "2") (pinfunction "2_2") (pintype "passive"))
    )
    (net (code "49") (name "Net-(J7-CC2)") (class "Default")
      (node (ref "J7") (pin "B5") (pinfunction "CC2_B5") (pintype "passive"))
      (node (ref "R16") (pin "2") (pinfunction "2_2") (pintype "passive"))
    )
    (net (code "50") (name "Net-(Q1-B)") (class "Default")
      (node (ref "Q1") (pin "1") (pinfunction "B_1") (pintype "passive"))
      (node (ref "R4") (pin "2") (pinfunction "2_2") (pintype "passive"))
    )
    (net (code "51") (name "Net-(Q2-B)") (class "Default")
      (node (ref "Q2") (pin "1") (pinfunction "B_1") (pintype "passive"))
      (node (ref "R19") (pin "2") (pinfunction "2_2") (pintype "passive"))
    )
    (net (code "52") (name "Net-(U4-CBUS0)") (class "Default")
      (node (ref "R14") (pin "1") (pinfunction "1_1") (pintype "passive"))
      (node (ref "U4") (pin "15") (pinfunction "CBUS0_15") (pintype "passive"))
    )
    (net (code "53") (name "unconnected-(HMC1-DRDY-Pad5)") (class "Default")
      (node (ref "HMC1") (pin "5") (pinfunction "DRDY_5") (pintype "passive"))
    )
    (net (code "54") (name "unconnected-(J1-DAT1-Pad8)") (class "Default")
      (node (ref "J1") (pin "8") (pinfunction "DAT1_8") (pintype "bidirectional"))
    )
    (net (code "55") (name "unconnected-(J1-DAT2-Pad1)") (class "Default")
      (node (ref "J1") (pin "1") (pinfunction "DAT2_1") (pintype "bidirectional"))
    )
    (net (code "56") (name "unconnected-(J7-SBU1-PadA8)") (class "Default")
      (node (ref "J7") (pin "A8") (pinfunction "SBU1_A8") (pintype "passive+no_connect"))
    )
    (net (code "57") (name "unconnected-(J7-SBU2-PadB8)") (class "Default")
      (node (ref "J7") (pin "B8") (pinfunction "SBU2_B8") (pintype "passive+no_connect"))
    )
    (net (code "58") (name "unconnected-(MPU1-Pad1)") (class "Default")
      (node (ref "MPU1") (pin "1") (pinfunction "1_1") (pintype "passive"))
    )
    (net (code "59") (name "unconnected-(MPU1-Pad2)") (class "Default")
      (node (ref "MPU1") (pin "2") (pinfunction "2_2") (pintype "passive"))
    )
    (net (code "60") (name "unconnected-(MPU1-Pad3)") (class "Default")
      (node (ref "MPU1") (pin "3") (pinfunction "3_3") (pintype "passive"))
    )
    (net (code "61") (name "unconnected-(MPU1-Pad4)") (class "Default")
      (node (ref "MPU1") (pin "4") (pinfunction "4_4") (pintype "passive"))
    )
    (net (code "62") (name "unconnected-(U1-IO3-Pad15)") (class "Default")
      (node (ref "U1") (pin "15") (pinfunction "IO3_15") (pintype "bidirectional"))
    )
    (net (code "63") (name "unconnected-(U1-IO16-Pad9)") (class "Default")
      (node (ref "U1") (pin "9") (pinfunction "IO16_9") (pintype "bidirectional"))
    )
    (net (code "64") (name "unconnected-(U1-IO17-Pad10)") (class "Default")
      (node (ref "U1") (pin "10") (pinfunction "IO17_10") (pintype "bidirectional"))
    )
    (net (code "65") (name "unconnected-(U1-IO18-Pad11)") (class "Default")
      (node (ref "U1") (pin "11") (pinfunction "IO18_11") (pintype "bidirectional"))
    )
    (net (code "66") (name "unconnected-(U1-IO21-Pad23)") (class "Default")
      (node (ref "U1") (pin "23") (pinfunction "IO21_23") (pintype "bidirectional"))
    )
    (net (code "67") (name "unconnected-(U1-IO45-Pad26)") (class "Default")
      (node (ref "U1") (pin "26") (pinfunction "IO45_26") (pintype "bidirectional"))
    )
    (net (code "68") (name "unconnected-(U1-IO46-Pad16)") (class "Default")
      (node (ref "U1") (pin "16") (pinfunction "IO46_16") (pintype "bidirectional"))
    )
    (net (code "69") (name "unconnected-(U1-IO47-Pad24)") (class "Default")
      (node (ref "U1") (pin "24") (pinfunction "IO47_24") (pintype "bidirectional"))
    )
    (net (code "70") (name "unconnected-(U1-IO48-Pad25)") (class "Default")
      (node (ref "U1") (pin "25") (pinfunction "IO48_25") (pintype "bidirectional"))
    )
    (net (code "71") (name "unconnected-(U2-PadCSB)") (class "Default")
      (node (ref "U2") (pin "CSB") (pintype "input+no_connect"))
    )
    (net (code "72") (name "unconnected-(U4-CBUS1-Pad14)") (class "Default")
      (node (ref "U4") (pin "14") (pinfunction "CBUS1_14") (pintype "passive+no_connect"))
    )
    (net (code "73") (name "unconnected-(U4-CBUS2-Pad7)") (class "Default")
      (node (ref "U4") (pin "7") (pinfunction "CBUS2_7") (pintype "passive+no_connect"))
    )
    (net (code "74") (name "unconnected-(U4-~{CTS}-Pad6)") (class "Default")
      (node (ref "U4") (pin "6") (pinfunction "~{CTS}_6") (pintype "passive+no_connect"))
    )
    (net (code "75") (name "unconnected-(U4-~{DCD}-Pad5)") (class "Default")
      (node (ref "U4") (pin "5") (pinfunction "~{DCD}_5") (pintype "passive+no_connect"))
    )
    (net (code "76") (name "unconnected-(U4-~{DSR}-Pad4)") (class "Default")
      (node (ref "U4") (pin "4") (pinfunction "~{DSR}_4") (pintype "passive+no_connect"))
    )
    (net (code "77") (name "unconnected-(U4-~{RI}-Pad2)") (class "Default")
      (node (ref "U4") (pin "2") (pinfunction "~{RI}_2") (pintype "passive+no_connect"))
    )
  )
)
